# NIBP_Board_v1_2_0_feb2023.net
KiCad netlist of a schematic drawn in EAGLE
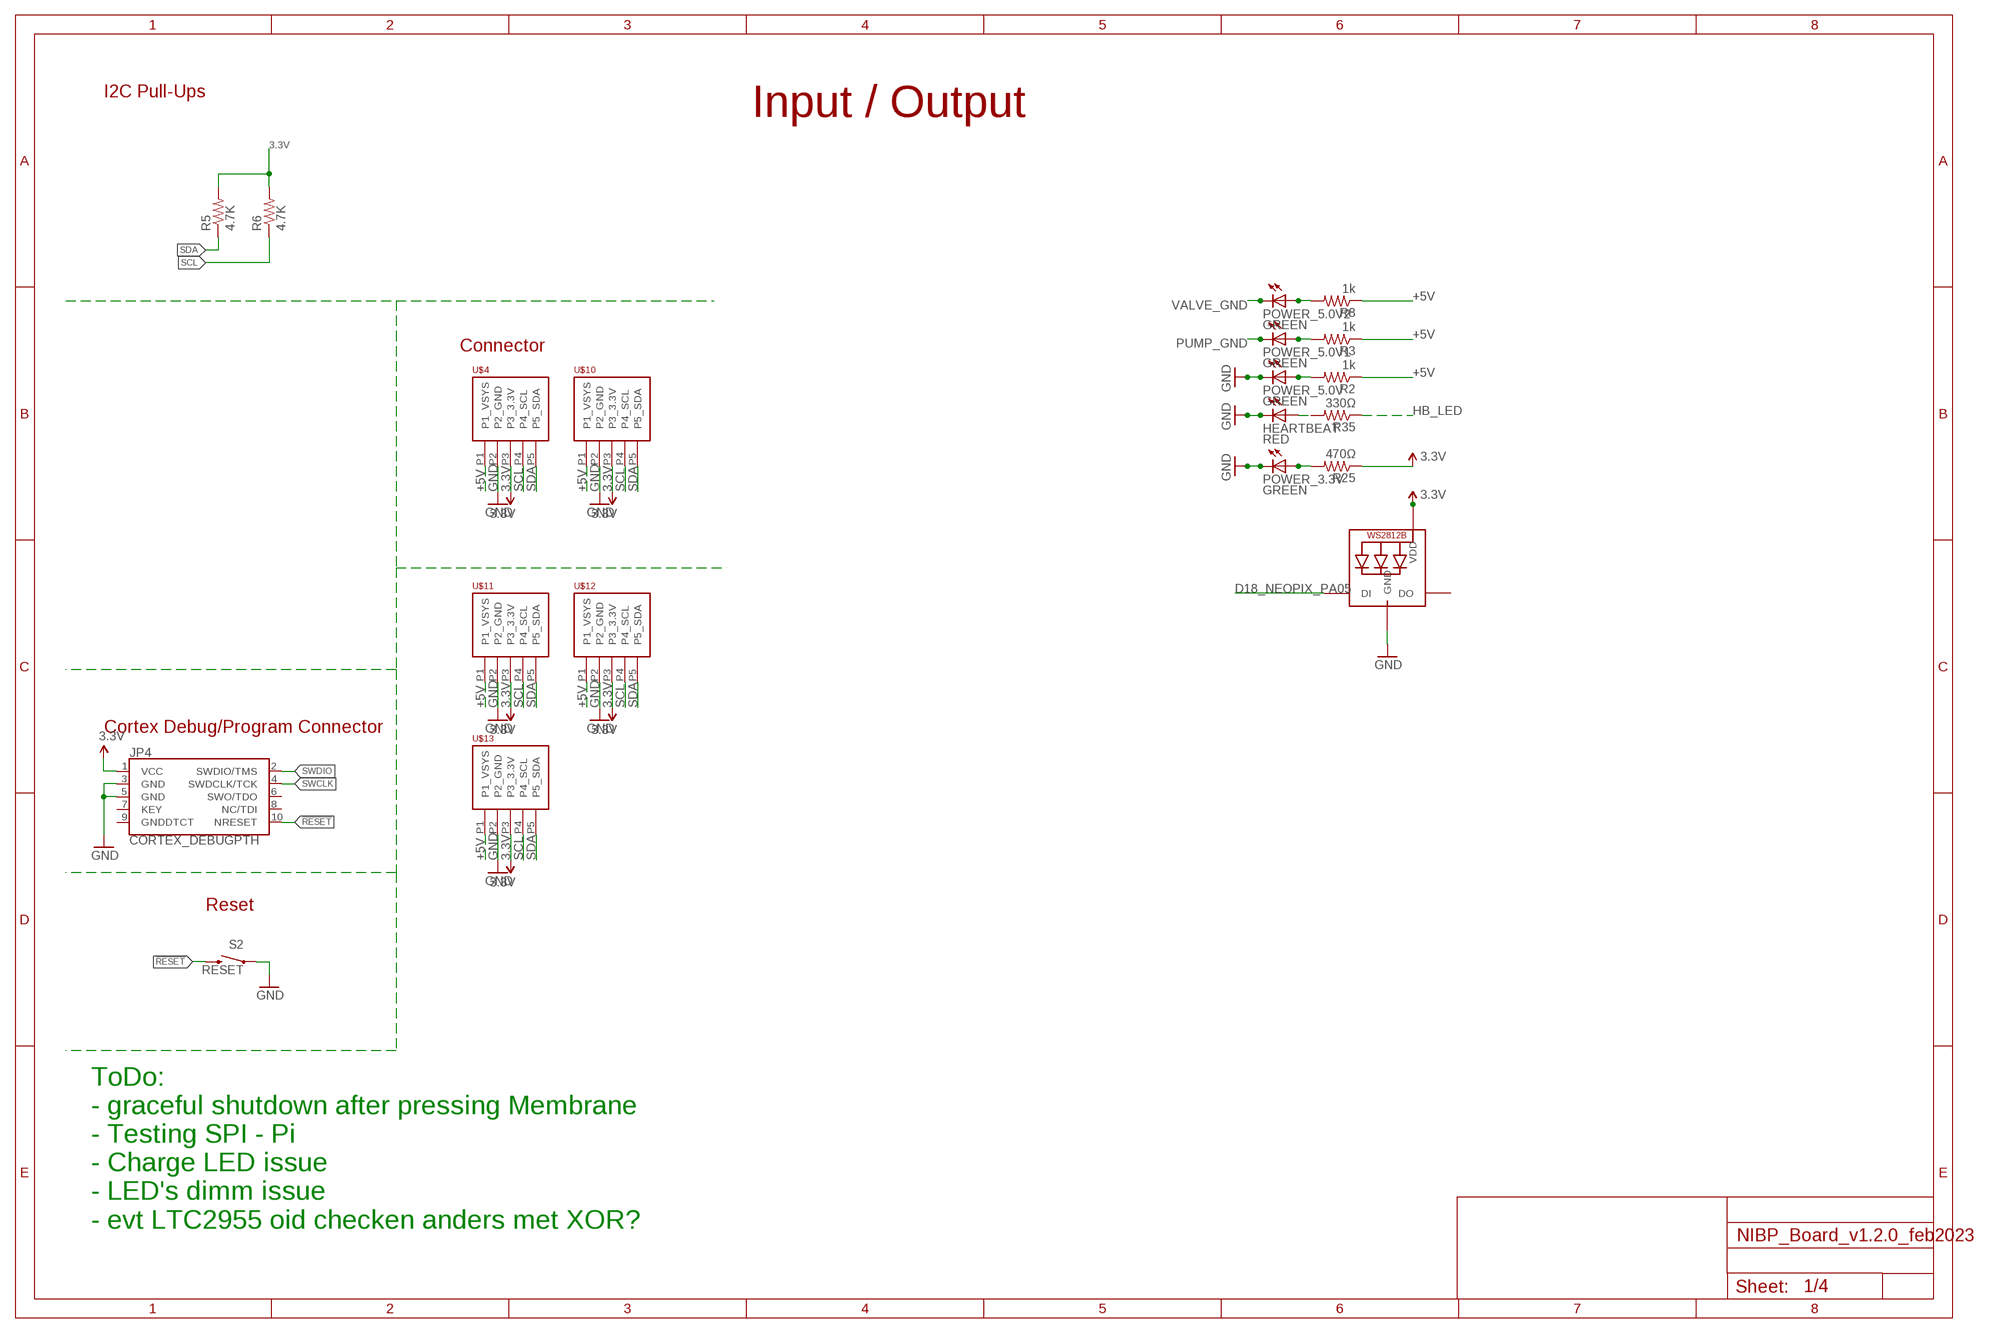
[diagram p0: schematic, sheet 1]
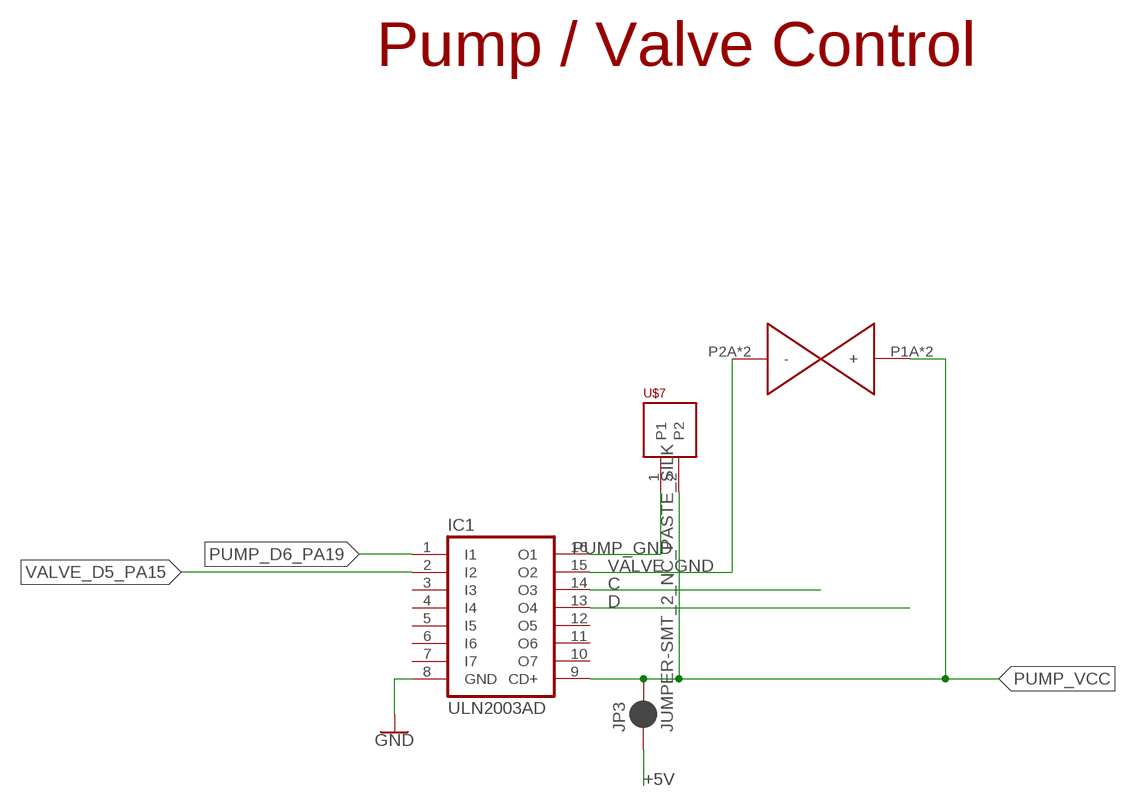
[diagram p1: schematic, sheet 2]
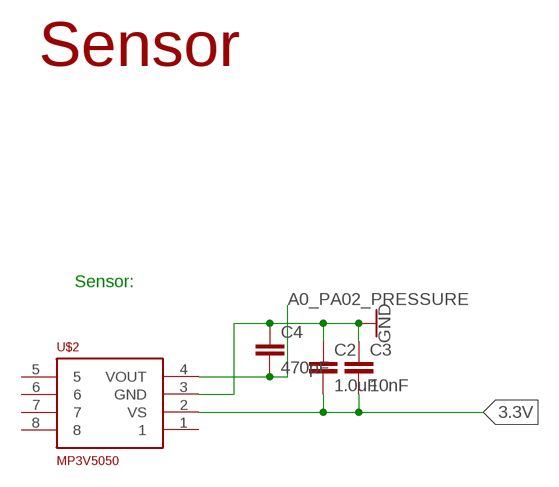
[diagram p2: schematic, sheet 3]
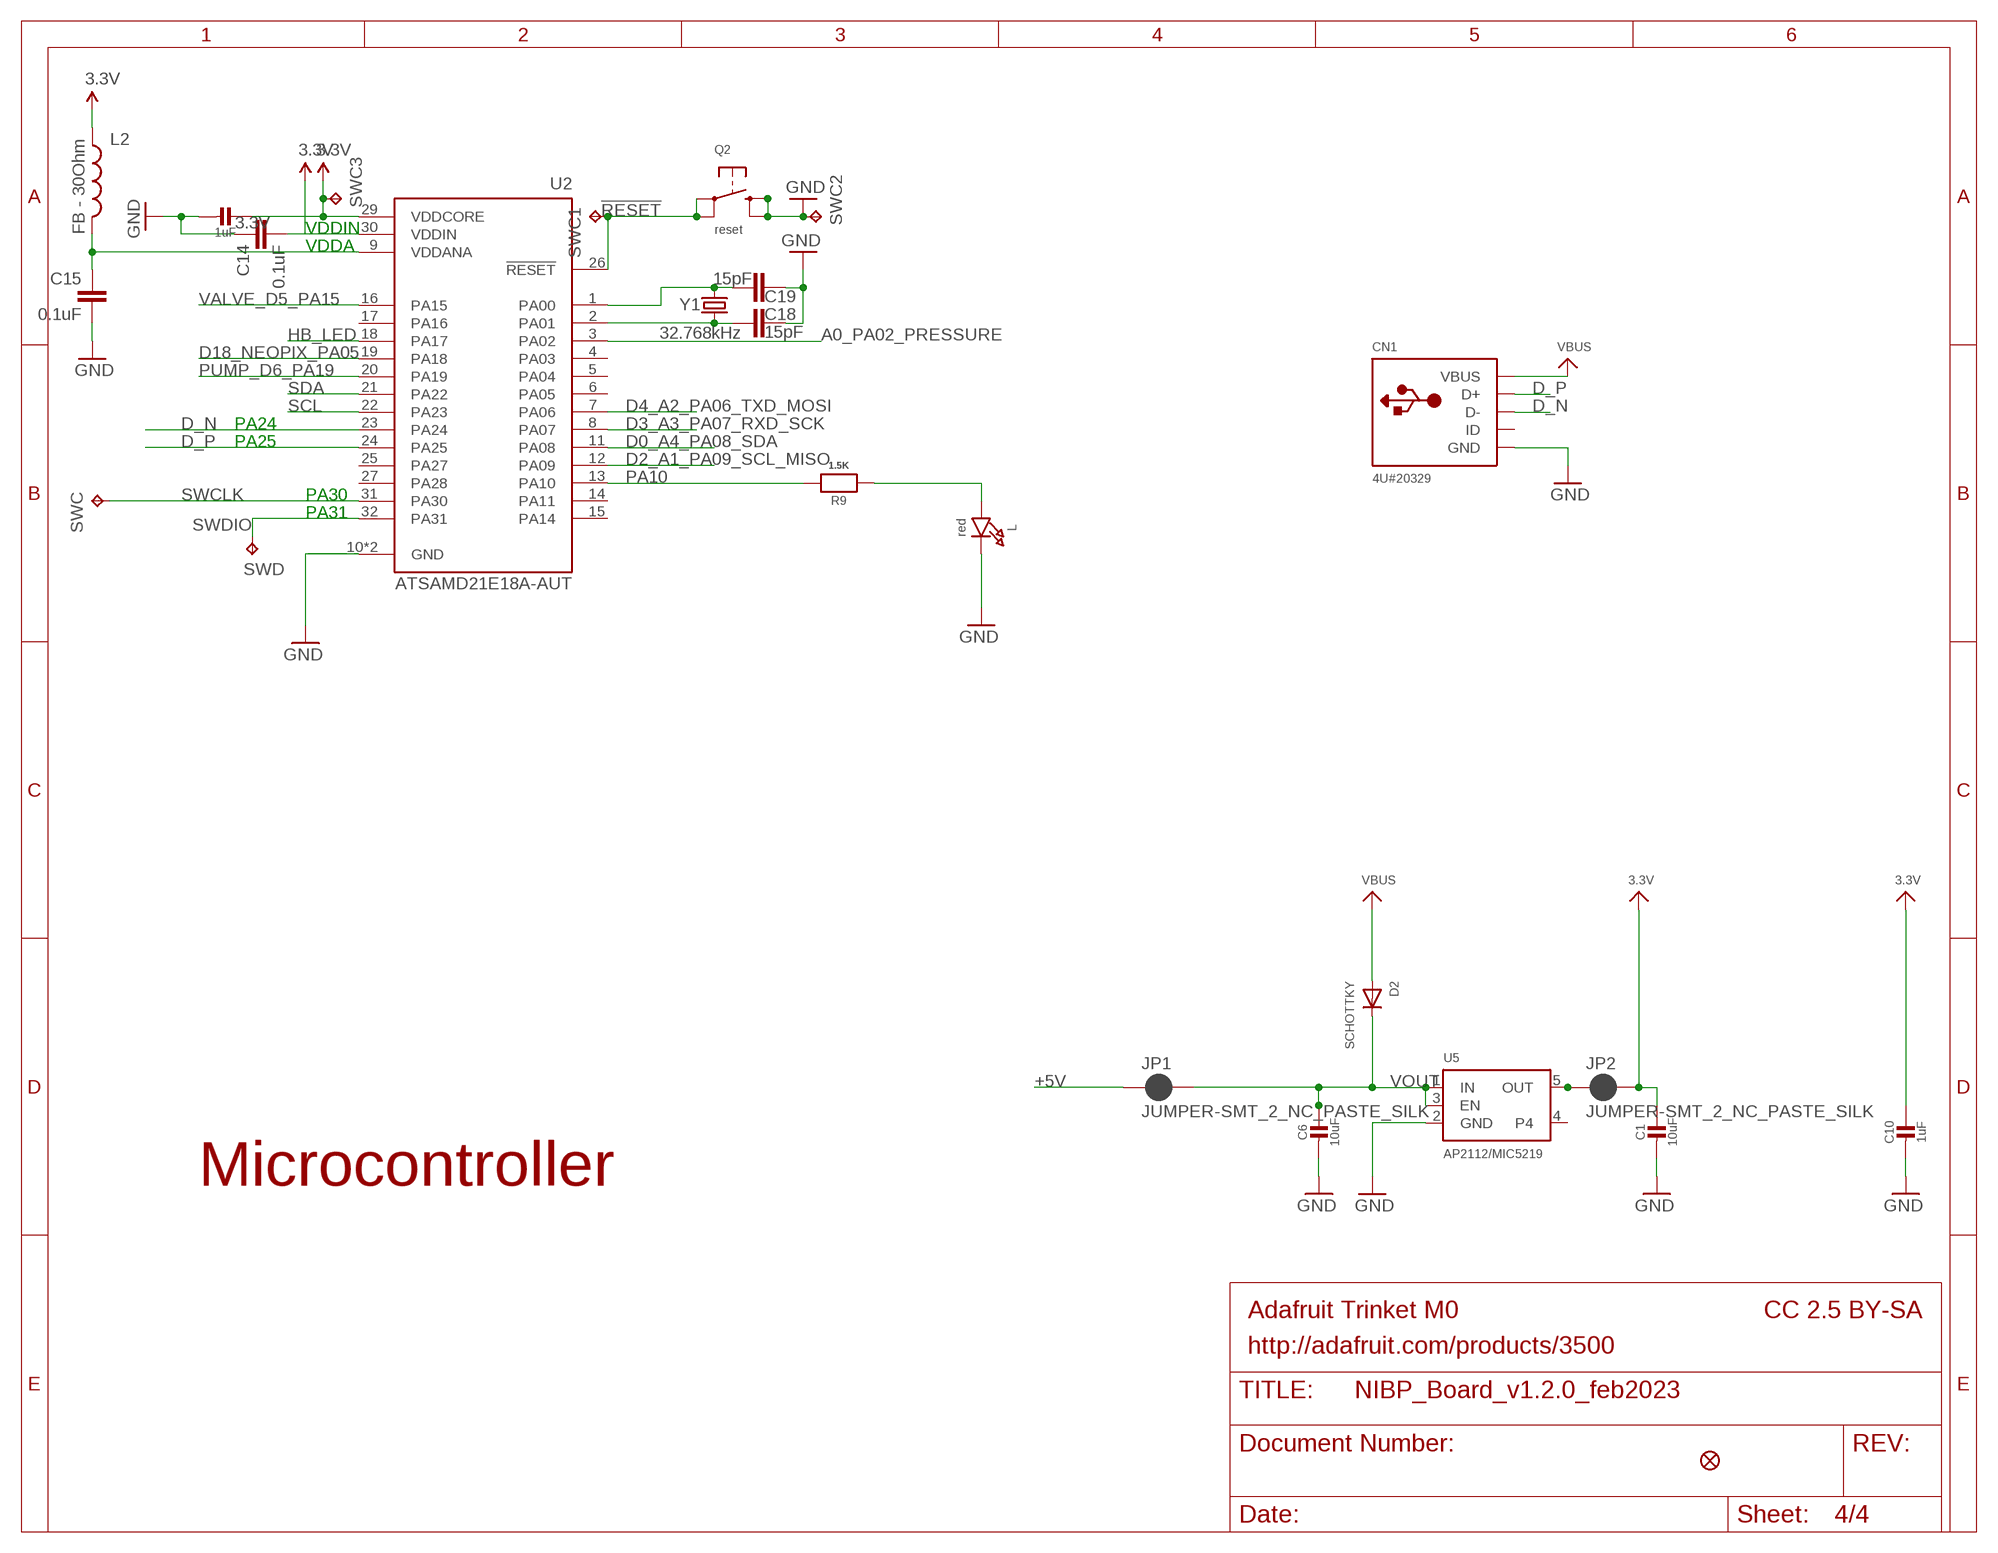
[diagram p3: schematic, sheet 4]

(export (version "E")
  (design (tool "Eeschema 10.0.6"))
  (components
    (comp (ref "C2")
      (value "1.0uF")
      (footprint "eagle-import:0603")
      (libsource (lib "eagle-import") (part "1.0UF-0603-16V-10%"))
    )
    (comp (ref "C3")
      (value "10nF")
      (footprint "eagle-import:0603")
      (libsource (lib "eagle-import") (part "10NF-0603-50V-10%"))
    )
    (comp (ref "C4")
      (value "470pF")
      (footprint "eagle-import:0603")
      (libsource (lib "eagle-import") (part "470PF-0603-50V-5%"))
    )
    (comp (ref "U$2")
      (value "MP3V5050")
      (footprint "eagle-import:PRESSURE_SENSOR")
      (libsource (lib "eagle-import") (part "MP3V5050"))
    )
    (comp (ref "C1")
      (value "10uF")
      (footprint "eagle-import:0805-NO")
      (libsource (lib "eagle-import") (part "CAP_CERAMIC0805-NOOUTLINE"))
    )
    (comp (ref "C6")
      (value "10uF")
      (footprint "eagle-import:0805-NO")
      (libsource (lib "eagle-import") (part "CAP_CERAMIC0805-NOOUTLINE"))
    )
    (comp (ref "C10")
      (value "1uF")
      (footprint "eagle-import:0603-NO")
      (libsource (lib "eagle-import") (part "CAP_CERAMIC0603_NO"))
    )
    (comp (ref "C13")
      (value "1uF")
      (footprint "eagle-import:0603-NO")
      (libsource (lib "eagle-import") (part "CAP_CERAMIC0603_NO"))
    )
    (comp (ref "C14")
      (value "0.1uF")
      (footprint "eagle-import:0402-CAP")
      (libsource (lib "eagle-import") (part "0.1UF-16V(+-10%)(0402)"))
    )
    (comp (ref "C15")
      (value "0.1uF")
      (footprint "eagle-import:0402-CAP")
      (libsource (lib "eagle-import") (part "0.1UF-16V(+-10%)(0402)"))
    )
    (comp (ref "C18")
      (value "15pF")
      (footprint "eagle-import:0402-CAP")
      (libsource (lib "eagle-import") (part "15PF-50V(+-5%)(0402)"))
    )
    (comp (ref "C19")
      (value "15pF")
      (footprint "eagle-import:0402-CAP")
      (libsource (lib "eagle-import") (part "15PF-50V(+-5%)(0402)"))
    )
    (comp (ref "CN1")
      (value "4U#20329")
      (footprint "eagle-import:4UCONN_20329_V2")
      (libsource (lib "eagle-import") (part "USB_MICRO_20329_V2"))
    )
    (comp (ref "D2")
      (value "SCHOTTKY")
      (footprint "eagle-import:SOD-123FL")
      (libsource (lib "eagle-import") (part "DIODE_SOD-123FL"))
    )
    (comp (ref "JP1")
      (value "JUMPER-SMT_2_NC_PASTE_SILK")
      (footprint "eagle-import:SMT-JUMPER_2_NC_PASTE_SILK")
      (libsource (lib "eagle-import") (part "JUMPER-SMT_2_NC_PASTE_SILK"))
    )
    (comp (ref "JP2")
      (value "JUMPER-SMT_2_NC_PASTE_SILK")
      (footprint "eagle-import:SMT-JUMPER_2_NC_PASTE_SILK")
      (libsource (lib "eagle-import") (part "JUMPER-SMT_2_NC_PASTE_SILK"))
    )
    (comp (ref "L")
      (value "red")
      (footprint "eagle-import:CHIPLED_0603_NOOUTLINE")
      (libsource (lib "eagle-import") (part "LED0603_NOOUTLINE"))
    )
    (comp (ref "L2")
      (value "FB - 30Ohm")
      (footprint "eagle-import:0603")
      (libsource (lib "eagle-import") (part "INDUCTOR0603"))
    )
    (comp (ref "Q2")
      (value "reset")
      (footprint "eagle-import:BTN_KMR2_4.6X2.8")
      (libsource (lib "eagle-import") (part "SWITCH_TACT_SMT4.6X2.8"))
    )
    (comp (ref "R9")
      (value "1.5K")
      (footprint "eagle-import:0603-NO")
      (libsource (lib "eagle-import") (part "RESISTOR_0603_NOOUT"))
    )
    (comp (ref "SWC")
      (value "TPB1,27")
      (footprint "eagle-import:B1,27")
      (libsource (lib "eagle-import") (part "TPB1,27"))
    )
    (comp (ref "SWC1")
      (value "TPB1,27")
      (footprint "eagle-import:B1,27")
      (libsource (lib "eagle-import") (part "TPB1,27"))
    )
    (comp (ref "SWC2")
      (value "TPB1,27")
      (footprint "eagle-import:B1,27")
      (libsource (lib "eagle-import") (part "TPB1,27"))
    )
    (comp (ref "SWC3")
      (value "TPB1,27")
      (footprint "eagle-import:B1,27")
      (libsource (lib "eagle-import") (part "TPB1,27"))
    )
    (comp (ref "SWD")
      (value "TPB1,27")
      (footprint "eagle-import:B1,27")
      (libsource (lib "eagle-import") (part "TPB1,27"))
    )
    (comp (ref "U$15")
      (value "FIDUCIAL_1MM")
      (footprint "eagle-import:FIDUCIAL_1MM")
      (libsource (lib "eagle-import") (part "FIDUCIAL_1MM"))
    )
    (comp (ref "U2")
      (value "ATSAMD21E18A-AUT")
      (footprint "eagle-import:QFP80P900X900X120-32N")
      (fields (field (name "MF") "Microchip") (field (name "MP") "ATSAMD21E18A-AU"))
      (libsource (lib "eagle-import") (part "ATSAMD21E18A-AUT"))
    )
    (comp (ref "U5")
      (value "AP2112/MIC5219")
      (footprint "eagle-import:SOT23-5")
      (libsource (lib "eagle-import") (part "VREG_SOT23-5"))
    )
    (comp (ref "Y1")
      (value "32.768kHz")
      (footprint "eagle-import:CRYSTAL-SMD-3.2X1.5MM")
      (libsource (lib "eagle-import") (part "CRYSTAL3.2X1.5MM"))
    )
    (comp (ref "IC1")
      (value "ULN2003AD")
      (footprint "eagle-import:SO16")
      (libsource (lib "eagle-import") (part "ULN2003AD"))
    )
    (comp (ref "JP3")
      (value "JUMPER-SMT_2_NC_PASTE_SILK")
      (footprint "eagle-import:SMT-JUMPER_2_NC_PASTE_SILK")
      (libsource (lib "eagle-import") (part "JUMPER-SMT_2_NC_PASTE_SILK"))
    )
    (comp (ref "U$6")
      (value "VALVE_NIBP")
      (footprint "eagle-import:VALVE_NIBP")
      (libsource (lib "eagle-import") (part "VALVE_NIBP"))
    )
    (comp (ref "U$7")
      (value "PHOENIX_PTSM_M2TH")
      (footprint "eagle-import:PTSM_M2_THRHOLE")
      (libsource (lib "eagle-import") (part "PHOENIX_PTSM_M2TH"))
    )
    (comp (ref "HEARTBEAT")
      (value "RED")
      (footprint "eagle-import:LED-0603")
      (libsource (lib "eagle-import") (part "LED0603"))
    )
    (comp (ref "JP4")
      (value "CORTEX_DEBUGPTH")
      (footprint "eagle-import:2X5-PTH-1.27MM")
      (libsource (lib "eagle-import") (part "CORTEX_DEBUGPTH"))
    )
    (comp (ref "LED1")
      (value "WS2812B3535")
      (footprint "eagle-import:LED3535")
      (libsource (lib "eagle-import") (part "WS2812B3535"))
    )
    (comp (ref "POWER_3.3V")
      (value "GREEN")
      (footprint "eagle-import:LED-0603")
      (libsource (lib "eagle-import") (part "LED0603"))
    )
    (comp (ref "POWER_5.0V")
      (value "GREEN")
      (footprint "eagle-import:LED-0603")
      (libsource (lib "eagle-import") (part "LED0603"))
    )
    (comp (ref "POWER_5.0V1")
      (value "GREEN")
      (footprint "eagle-import:LED-0603")
      (libsource (lib "eagle-import") (part "LED0603"))
    )
    (comp (ref "POWER_5.0V2")
      (value "GREEN")
      (footprint "eagle-import:LED-0603")
      (libsource (lib "eagle-import") (part "LED0603"))
    )
    (comp (ref "R2")
      (value "1k")
      (footprint "eagle-import:0603-RES")
      (libsource (lib "eagle-import") (part "10KOHM-1/10W-1%(0603)0603"))
    )
    (comp (ref "R3")
      (value "1k")
      (footprint "eagle-import:0603-RES")
      (libsource (lib "eagle-import") (part "10KOHM-1/10W-1%(0603)0603"))
    )
    (comp (ref "R5")
      (value "4.7K")
      (footprint "eagle-import:0603-RES@1")
      (libsource (lib "eagle-import") (part "4.7KOHM-1/10W-1%(0603)"))
    )
    (comp (ref "R6")
      (value "4.7K")
      (footprint "eagle-import:0603-RES@1")
      (libsource (lib "eagle-import") (part "4.7KOHM-1/10W-1%(0603)"))
    )
    (comp (ref "R8")
      (value "1k")
      (footprint "eagle-import:0603-RES")
      (libsource (lib "eagle-import") (part "10KOHM-1/10W-1%(0603)0603"))
    )
    (comp (ref "R25")
      (value "470Ω")
      (footprint "eagle-import:0603-RES")
      (libsource (lib "eagle-import") (part "10KOHM-1/10W-1%(0603)0603"))
    )
    (comp (ref "R35")
      (value "330Ω")
      (footprint "eagle-import:0603-RES")
      (libsource (lib "eagle-import") (part "10KOHM-1/10W-1%(0603)0603"))
    )
    (comp (ref "S2")
      (value "RESET")
      (footprint "eagle-import:TACTILE_SWITCH_SMD_4.6X2.8MM")
      (libsource (lib "eagle-import") (part "SWITCH-MOMENTARY-2SMD-4.6X2.8MM"))
    )
    (comp (ref "U$4")
      (value "PHOENIX_PTSM_M5_TH")
      (footprint "eagle-import:PTSM_M5_THRHOLE")
      (libsource (lib "eagle-import") (part "PHOENIX_PTSM_M5_TH"))
    )
    (comp (ref "U$10")
      (value "PHOENIX_PTSM_M5_TH")
      (footprint "eagle-import:PTSM_M5_THRHOLE")
      (libsource (lib "eagle-import") (part "PHOENIX_PTSM_M5_TH"))
    )
    (comp (ref "U$11")
      (value "PHOENIX_PTSM_M5_TH")
      (footprint "eagle-import:PTSM_M5_THRHOLE")
      (libsource (lib "eagle-import") (part "PHOENIX_PTSM_M5_TH"))
    )
    (comp (ref "U$12")
      (value "PHOENIX_PTSM_M5_TH")
      (footprint "eagle-import:PTSM_M5_THRHOLE")
      (libsource (lib "eagle-import") (part "PHOENIX_PTSM_M5_TH"))
    )
    (comp (ref "U$13")
      (value "PHOENIX_PTSM_M5_TH")
      (footprint "eagle-import:PTSM_M5_THRHOLE")
      (libsource (lib "eagle-import") (part "PHOENIX_PTSM_M5_TH"))
    )
  )
  (nets
    (net (code "1") (name "+5V") (class "Default")
      (node (ref "JP1") (pin "1") (pinfunction "1_1") (pintype "passive"))
      (node (ref "JP3") (pin "1") (pinfunction "1_1") (pintype "passive"))
      (node (ref "R2") (pin "1") (pinfunction "1_1") (pintype "passive"))
      (node (ref "R3") (pin "1") (pinfunction "1_1") (pintype "passive"))
      (node (ref "R8") (pin "1") (pinfunction "1_1") (pintype "passive"))
      (node (ref "U$10") (pin "P1") (pinfunction "P1_VSYS_P1") (pintype "power_in"))
      (node (ref "U$11") (pin "P1") (pinfunction "P1_VSYS_P1") (pintype "power_in"))
      (node (ref "U$12") (pin "P1") (pinfunction "P1_VSYS_P1") (pintype "power_in"))
      (node (ref "U$13") (pin "P1") (pinfunction "P1_VSYS_P1") (pintype "power_in"))
      (node (ref "U$4") (pin "P1") (pinfunction "P1_VSYS_P1") (pintype "power_in"))
    )
    (net (code "2") (name "3.3V") (class "Default")
      (node (ref "C1") (pin "1") (pinfunction "1_1") (pintype "passive"))
      (node (ref "C10") (pin "1") (pinfunction "1_1") (pintype "passive"))
      (node (ref "C13") (pin "1") (pinfunction "1_1") (pintype "passive"))
      (node (ref "C2") (pin "2") (pinfunction "2_2") (pintype "passive"))
      (node (ref "C3") (pin "2") (pinfunction "2_2") (pintype "passive"))
      (node (ref "JP2") (pin "2") (pinfunction "2_2") (pintype "passive"))
      (node (ref "JP4") (pin "1") (pinfunction "VCC_1") (pintype "bidirectional"))
      (node (ref "L2") (pin "1") (pinfunction "1_1") (pintype "passive"))
      (node (ref "LED1") (pin "2") (pinfunction "VDD_2") (pintype "power_in"))
      (node (ref "R25") (pin "1") (pinfunction "1_1") (pintype "passive"))
      (node (ref "R5") (pin "2") (pinfunction "2_2") (pintype "passive"))
      (node (ref "R6") (pin "2") (pinfunction "2_2") (pintype "passive"))
      (node (ref "SWC3") (pin "TP") (pinfunction "TP_TP") (pintype "input"))
      (node (ref "U$10") (pin "P3") (pinfunction "P3_3.3V_P3") (pintype "power_in"))
      (node (ref "U$11") (pin "P3") (pinfunction "P3_3.3V_P3") (pintype "power_in"))
      (node (ref "U$12") (pin "P3") (pinfunction "P3_3.3V_P3") (pintype "power_in"))
      (node (ref "U$13") (pin "P3") (pinfunction "P3_3.3V_P3") (pintype "power_in"))
      (node (ref "U$2") (pin "2") (pinfunction "VS_2") (pintype "bidirectional"))
      (node (ref "U$4") (pin "P3") (pinfunction "P3_3.3V_P3") (pintype "power_in"))
      (node (ref "U2") (pin "29") (pinfunction "VDDCORE_29") (pintype "power_in"))
    )
    (net (code "3") (name "A0_PA02_PRESSURE") (class "Default")
      (node (ref "C4") (pin "2") (pinfunction "2_2") (pintype "passive"))
      (node (ref "U$2") (pin "4") (pinfunction "VOUT_4") (pintype "bidirectional"))
      (node (ref "U2") (pin "3") (pinfunction "PA02_3") (pintype "bidirectional"))
    )
    (net (code "4") (name "C") (class "Default")
      (node (ref "IC1") (pin "14") (pinfunction "O3_14") (pintype "open_collector"))
    )
    (net (code "5") (name "D") (class "Default")
      (node (ref "IC1") (pin "13") (pinfunction "O4_13") (pintype "open_collector"))
    )
    (net (code "6") (name "D0_A4_PA08_SDA") (class "Default")
      (node (ref "U2") (pin "11") (pinfunction "PA08_11") (pintype "bidirectional"))
    )
    (net (code "7") (name "D2_A1_PA09_SCL_MISO") (class "Default")
      (node (ref "U2") (pin "12") (pinfunction "PA09_12") (pintype "bidirectional"))
    )
    (net (code "8") (name "D3_A3_PA07_RXD_SCK") (class "Default")
      (node (ref "U2") (pin "8") (pinfunction "PA07_8") (pintype "bidirectional"))
    )
    (net (code "9") (name "D4_A2_PA06_TXD_MOSI") (class "Default")
      (node (ref "U2") (pin "7") (pinfunction "PA06_7") (pintype "bidirectional"))
    )
    (net (code "10") (name "D18_NEOPIX_PA05") (class "Default")
      (node (ref "LED1") (pin "1") (pinfunction "DI_1") (pintype "input"))
      (node (ref "U2") (pin "19") (pinfunction "PA18_19") (pintype "bidirectional"))
    )
    (net (code "11") (name "D_N") (class "Default")
      (node (ref "CN1") (pin "D-") (pinfunction "D-_D-") (pintype "bidirectional"))
      (node (ref "U2") (pin "23") (pinfunction "PA24_23") (pintype "bidirectional"))
    )
    (net (code "12") (name "D_P") (class "Default")
      (node (ref "CN1") (pin "D+") (pinfunction "D+_D+") (pintype "bidirectional"))
      (node (ref "U2") (pin "24") (pinfunction "PA25_24") (pintype "bidirectional"))
    )
    (net (code "13") (name "GND") (class "Default")
      (node (ref "C1") (pin "2") (pinfunction "2_2") (pintype "passive"))
      (node (ref "C10") (pin "2") (pinfunction "2_2") (pintype "passive"))
      (node (ref "C13") (pin "2") (pinfunction "2_2") (pintype "passive"))
      (node (ref "C14") (pin "1") (pinfunction "1_1") (pintype "passive"))
      (node (ref "C15") (pin "2") (pinfunction "2_2") (pintype "passive"))
      (node (ref "C18") (pin "1") (pinfunction "1_1") (pintype "passive"))
      (node (ref "C19") (pin "2") (pinfunction "2_2") (pintype "passive"))
      (node (ref "C2") (pin "1") (pinfunction "1_1") (pintype "passive"))
      (node (ref "C3") (pin "1") (pinfunction "1_1") (pintype "passive"))
      (node (ref "C4") (pin "1") (pinfunction "1_1") (pintype "passive"))
      (node (ref "C6") (pin "2") (pinfunction "2_2") (pintype "passive"))
      (node (ref "CN1") (pin "BASE@1") (pinfunction "GND_BASE@1") (pintype "power_in"))
      (node (ref "CN1") (pin "BASE@2") (pinfunction "GND_BASE@2") (pintype "power_in"))
      (node (ref "CN1") (pin "GND") (pinfunction "GND_GND") (pintype "power_in"))
      (node (ref "CN1") (pin "SPRT@1") (pinfunction "GND_SPRT@1") (pintype "power_in"))
      (node (ref "CN1") (pin "SPRT@2") (pinfunction "GND_SPRT@2") (pintype "power_in"))
      (node (ref "CN1") (pin "SPRT@3") (pinfunction "GND_SPRT@3") (pintype "power_in"))
      (node (ref "CN1") (pin "SPRT@4") (pinfunction "GND_SPRT@4") (pintype "power_in"))
      (node (ref "HEARTBEAT") (pin "C") (pinfunction "C_C") (pintype "passive"))
      (node (ref "IC1") (pin "8") (pinfunction "GND_8") (pintype "power_in"))
      (node (ref "JP4") (pin "3") (pinfunction "GND_3") (pintype "bidirectional"))
      (node (ref "JP4") (pin "5") (pinfunction "GND_5") (pintype "bidirectional"))
      (node (ref "L") (pin "C") (pinfunction "C_C") (pintype "passive"))
      (node (ref "LED1") (pin "4") (pinfunction "GND_4") (pintype "power_in"))
      (node (ref "POWER_3.3V") (pin "C") (pinfunction "C_C") (pintype "passive"))
      (node (ref "POWER_5.0V") (pin "C") (pinfunction "C_C") (pintype "passive"))
      (node (ref "Q2") (pin "B") (pinfunction "S_B") (pintype "passive"))
      (node (ref "Q2") (pin "B'") (pinfunction "S1_B'") (pintype "passive"))
      (node (ref "S2") (pin "1") (pinfunction "1_1") (pintype "passive"))
      (node (ref "S2") (pin "2") (pinfunction "1_2") (pintype "passive"))
      (node (ref "SWC2") (pin "TP") (pinfunction "TP_TP") (pintype "input"))
      (node (ref "U$10") (pin "P2") (pinfunction "P2_GND_P2") (pintype "power_in"))
      (node (ref "U$11") (pin "P2") (pinfunction "P2_GND_P2") (pintype "power_in"))
      (node (ref "U$12") (pin "P2") (pinfunction "P2_GND_P2") (pintype "power_in"))
      (node (ref "U$13") (pin "P2") (pinfunction "P2_GND_P2") (pintype "power_in"))
      (node (ref "U$2") (pin "3") (pinfunction "GND_3") (pintype "bidirectional"))
      (node (ref "U$4") (pin "P2") (pinfunction "P2_GND_P2") (pintype "power_in"))
      (node (ref "U2") (pin "10") (pinfunction "GND_10") (pintype "power_in"))
      (node (ref "U2") (pin "28") (pinfunction "GND_28") (pintype "power_in"))
      (node (ref "U5") (pin "2") (pinfunction "GND_2") (pintype "power_in"))
    )
    (net (code "14") (name "HB_LED") (class "Default")
      (node (ref "R35") (pin "1") (pinfunction "1_1") (pintype "passive"))
      (node (ref "U2") (pin "18") (pinfunction "PA17_18") (pintype "bidirectional"))
    )
    (net (code "15") (name "Net-(HEARTBEAT-PadA)") (class "Default")
      (node (ref "HEARTBEAT") (pin "A") (pinfunction "A_A") (pintype "passive"))
      (node (ref "R35") (pin "2") (pinfunction "2_2") (pintype "passive"))
    )
    (net (code "16") (name "Net-(L-PadA)") (class "Default")
      (node (ref "L") (pin "A") (pinfunction "A_A") (pintype "passive"))
      (node (ref "R9") (pin "1") (pinfunction "1_1") (pintype "passive"))
    )
    (net (code "17") (name "Net-(POWER_3.3V-PadA)") (class "Default")
      (node (ref "POWER_3.3V") (pin "A") (pinfunction "A_A") (pintype "passive"))
      (node (ref "R25") (pin "2") (pinfunction "2_2") (pintype "passive"))
    )
    (net (code "18") (name "Net-(POWER_5.0V-PadA)") (class "Default")
      (node (ref "POWER_5.0V") (pin "A") (pinfunction "A_A") (pintype "passive"))
      (node (ref "R2") (pin "2") (pinfunction "2_2") (pintype "passive"))
    )
    (net (code "19") (name "Net-(POWER_5.0V1-PadA)") (class "Default")
      (node (ref "POWER_5.0V1") (pin "A") (pinfunction "A_A") (pintype "passive"))
      (node (ref "R3") (pin "2") (pinfunction "2_2") (pintype "passive"))
    )
    (net (code "20") (name "Net-(POWER_5.0V2-PadA)") (class "Default")
      (node (ref "POWER_5.0V2") (pin "A") (pinfunction "A_A") (pintype "passive"))
      (node (ref "R8") (pin "2") (pinfunction "2_2") (pintype "passive"))
    )
    (net (code "21") (name "Net-(U2-PA00)") (class "Default")
      (node (ref "C19") (pin "1") (pinfunction "1_1") (pintype "passive"))
      (node (ref "U2") (pin "1") (pinfunction "PA00_1") (pintype "bidirectional"))
      (node (ref "Y1") (pin "P$1") (pinfunction "1_P$1") (pintype "passive"))
    )
    (net (code "22") (name "Net-(U2-PA01)") (class "Default")
      (node (ref "C18") (pin "2") (pinfunction "2_2") (pintype "passive"))
      (node (ref "U2") (pin "2") (pinfunction "PA01_2") (pintype "bidirectional"))
      (node (ref "Y1") (pin "P$2") (pinfunction "2_P$2") (pintype "passive"))
    )
    (net (code "23") (name "Net-(U2-VDDANA)") (class "Default")
      (node (ref "C15") (pin "1") (pinfunction "1_1") (pintype "passive"))
      (node (ref "L2") (pin "2") (pinfunction "2_2") (pintype "passive"))
      (node (ref "U2") (pin "9") (pinfunction "VDDANA_9") (pintype "power_in"))
    )
    (net (code "24") (name "Net-(U2-VDDIN)") (class "Default")
      (node (ref "C14") (pin "2") (pinfunction "2_2") (pintype "passive"))
      (node (ref "U2") (pin "30") (pinfunction "VDDIN_30") (pintype "power_in"))
    )
    (net (code "25") (name "Net-(U5-OUT)") (class "Default")
      (node (ref "JP2") (pin "1") (pinfunction "1_1") (pintype "passive"))
      (node (ref "U5") (pin "5") (pinfunction "OUT_5") (pintype "power_in"))
    )
    (net (code "26") (name "PA10") (class "Default")
      (node (ref "R9") (pin "2") (pinfunction "2_2") (pintype "passive"))
      (node (ref "U2") (pin "13") (pinfunction "PA10_13") (pintype "bidirectional"))
    )
    (net (code "27") (name "PUMP_D6_PA19") (class "Default")
      (node (ref "IC1") (pin "1") (pinfunction "I1_1") (pintype "input"))
      (node (ref "U2") (pin "20") (pinfunction "PA19_20") (pintype "bidirectional"))
    )
    (net (code "28") (name "PUMP_GND") (class "Default")
      (node (ref "IC1") (pin "16") (pinfunction "O1_16") (pintype "open_collector"))
      (node (ref "POWER_5.0V1") (pin "C") (pinfunction "C_C") (pintype "passive"))
      (node (ref "U$7") (pin "1") (pinfunction "P1_1") (pintype "bidirectional"))
    )
    (net (code "29") (name "PUMP_VCC") (class "Default")
      (node (ref "IC1") (pin "9") (pinfunction "CD+_9") (pintype "passive"))
      (node (ref "JP3") (pin "2") (pinfunction "2_2") (pintype "passive"))
      (node (ref "U$6") (pin "P1A") (pinfunction "+_P1A") (pintype "power_in"))
      (node (ref "U$6") (pin "P1B") (pinfunction "+_P1B") (pintype "power_in"))
      (node (ref "U$7") (pin "2") (pinfunction "P2_2") (pintype "bidirectional"))
    )
    (net (code "30") (name "SCL") (class "Default")
      (node (ref "R6") (pin "1") (pinfunction "1_1") (pintype "passive"))
      (node (ref "U$10") (pin "P4") (pinfunction "P4_SCL_P4") (pintype "bidirectional"))
      (node (ref "U$11") (pin "P4") (pinfunction "P4_SCL_P4") (pintype "bidirectional"))
      (node (ref "U$12") (pin "P4") (pinfunction "P4_SCL_P4") (pintype "bidirectional"))
      (node (ref "U$13") (pin "P4") (pinfunction "P4_SCL_P4") (pintype "bidirectional"))
      (node (ref "U$4") (pin "P4") (pinfunction "P4_SCL_P4") (pintype "bidirectional"))
      (node (ref "U2") (pin "22") (pinfunction "PA23_22") (pintype "bidirectional"))
    )
    (net (code "31") (name "SDA") (class "Default")
      (node (ref "R5") (pin "1") (pinfunction "1_1") (pintype "passive"))
      (node (ref "U$10") (pin "P5") (pinfunction "P5_SDA_P5") (pintype "bidirectional"))
      (node (ref "U$11") (pin "P5") (pinfunction "P5_SDA_P5") (pintype "bidirectional"))
      (node (ref "U$12") (pin "P5") (pinfunction "P5_SDA_P5") (pintype "bidirectional"))
      (node (ref "U$13") (pin "P5") (pinfunction "P5_SDA_P5") (pintype "bidirectional"))
      (node (ref "U$4") (pin "P5") (pinfunction "P5_SDA_P5") (pintype "bidirectional"))
      (node (ref "U2") (pin "21") (pinfunction "PA22_21") (pintype "bidirectional"))
    )
    (net (code "32") (name "SWCLK") (class "Default")
      (node (ref "JP4") (pin "4") (pinfunction "SWDCLK/TCK_4") (pintype "bidirectional"))
      (node (ref "SWC") (pin "TP") (pinfunction "TP_TP") (pintype "input"))
      (node (ref "U2") (pin "31") (pinfunction "PA30_31") (pintype "bidirectional"))
    )
    (net (code "33") (name "SWDIO") (class "Default")
      (node (ref "JP4") (pin "2") (pinfunction "SWDIO/TMS_2") (pintype "bidirectional"))
      (node (ref "SWD") (pin "TP") (pinfunction "TP_TP") (pintype "input"))
      (node (ref "U2") (pin "32") (pinfunction "PA31_32") (pintype "bidirectional"))
    )
    (net (code "34") (name "VALVE_D5_PA15") (class "Default")
      (node (ref "IC1") (pin "2") (pinfunction "I2_2") (pintype "input"))
      (node (ref "U2") (pin "16") (pinfunction "PA15_16") (pintype "bidirectional"))
    )
    (net (code "35") (name "VALVE_GND") (class "Default")
      (node (ref "IC1") (pin "15") (pinfunction "O2_15") (pintype "open_collector"))
      (node (ref "POWER_5.0V2") (pin "C") (pinfunction "C_C") (pintype "passive"))
      (node (ref "U$6") (pin "P2A") (pinfunction "-_P2A") (pintype "power_in"))
      (node (ref "U$6") (pin "P2B") (pinfunction "-_P2B") (pintype "power_in"))
    )
    (net (code "36") (name "VBUS") (class "Default")
      (node (ref "CN1") (pin "VBUS") (pinfunction "VBUS_VBUS") (pintype "power_in"))
      (node (ref "D2") (pin "A") (pinfunction "A_A") (pintype "passive"))
    )
    (net (code "37") (name "VOUT") (class "Default")
      (node (ref "C6") (pin "1") (pinfunction "1_1") (pintype "passive"))
      (node (ref "D2") (pin "C") (pinfunction "C_C") (pintype "passive"))
      (node (ref "JP1") (pin "2") (pinfunction "2_2") (pintype "passive"))
      (node (ref "U5") (pin "1") (pinfunction "IN_1") (pintype "power_in"))
      (node (ref "U5") (pin "3") (pinfunction "EN_3") (pintype "input"))
    )
    (net (code "38") (name "unconnected-(CN1-PadID)") (class "Default")
      (node (ref "CN1") (pin "ID") (pinfunction "ID_ID") (pintype "bidirectional"))
    )
    (net (code "39") (name "unconnected-(IC1-I3-Pad3)") (class "Default")
      (node (ref "IC1") (pin "3") (pinfunction "I3_3") (pintype "input"))
    )
    (net (code "40") (name "unconnected-(IC1-I4-Pad4)") (class "Default")
      (node (ref "IC1") (pin "4") (pinfunction "I4_4") (pintype "input"))
    )
    (net (code "41") (name "unconnected-(IC1-I5-Pad5)") (class "Default")
      (node (ref "IC1") (pin "5") (pinfunction "I5_5") (pintype "input"))
    )
    (net (code "42") (name "unconnected-(IC1-I6-Pad6)") (class "Default")
      (node (ref "IC1") (pin "6") (pinfunction "I6_6") (pintype "input"))
    )
    (net (code "43") (name "unconnected-(IC1-I7-Pad7)") (class "Default")
      (node (ref "IC1") (pin "7") (pinfunction "I7_7") (pintype "input"))
    )
    (net (code "44") (name "unconnected-(IC1-O5-Pad12)") (class "Default")
      (node (ref "IC1") (pin "12") (pinfunction "O5_12") (pintype "open_collector"))
    )
    (net (code "45") (name "unconnected-(IC1-O6-Pad11)") (class "Default")
      (node (ref "IC1") (pin "11") (pinfunction "O6_11") (pintype "open_collector"))
    )
    (net (code "46") (name "unconnected-(IC1-O7-Pad10)") (class "Default")
      (node (ref "IC1") (pin "10") (pinfunction "O7_10") (pintype "open_collector"))
    )
    (net (code "47") (name "unconnected-(JP4-GNDDTCT-Pad9)") (class "Default")
      (node (ref "JP4") (pin "9") (pinfunction "GNDDTCT_9") (pintype "bidirectional"))
    )
    (net (code "48") (name "unconnected-(JP4-KEY-Pad7)") (class "Default")
      (node (ref "JP4") (pin "7") (pinfunction "KEY_7") (pintype "bidirectional"))
    )
    (net (code "49") (name "unconnected-(JP4-NC{slash}TDI-Pad8)") (class "Default")
      (node (ref "JP4") (pin "8") (pinfunction "NC/TDI_8") (pintype "bidirectional"))
    )
    (net (code "50") (name "unconnected-(JP4-SWO{slash}TDO-Pad6)") (class "Default")
      (node (ref "JP4") (pin "6") (pinfunction "SWO/TDO_6") (pintype "bidirectional"))
    )
    (net (code "51") (name "unconnected-(LED1-DO-Pad3)") (class "Default")
      (node (ref "LED1") (pin "3") (pinfunction "DO_3") (pintype "output"))
    )
    (net (code "52") (name "unconnected-(U$2-Pad1)") (class "Default")
      (node (ref "U$2") (pin "1") (pinfunction "1_1") (pintype "no_connect"))
    )
    (net (code "53") (name "unconnected-(U$2-Pad5)") (class "Default")
      (node (ref "U$2") (pin "5") (pinfunction "5_5") (pintype "no_connect"))
    )
    (net (code "54") (name "unconnected-(U$2-Pad6)") (class "Default")
      (node (ref "U$2") (pin "6") (pinfunction "6_6") (pintype "no_connect"))
    )
    (net (code "55") (name "unconnected-(U$2-Pad7)") (class "Default")
      (node (ref "U$2") (pin "7") (pinfunction "7_7") (pintype "no_connect"))
    )
    (net (code "56") (name "unconnected-(U$2-Pad8)") (class "Default")
      (node (ref "U$2") (pin "8") (pinfunction "8_8") (pintype "no_connect"))
    )
    (net (code "57") (name "unconnected-(U2-PA03-Pad4)") (class "Default")
      (node (ref "U2") (pin "4") (pinfunction "PA03_4") (pintype "bidirectional"))
    )
    (net (code "58") (name "unconnected-(U2-PA04-Pad5)") (class "Default")
      (node (ref "U2") (pin "5") (pinfunction "PA04_5") (pintype "bidirectional"))
    )
    (net (code "59") (name "unconnected-(U2-PA05-Pad6)") (class "Default")
      (node (ref "U2") (pin "6") (pinfunction "PA05_6") (pintype "bidirectional"))
    )
    (net (code "60") (name "unconnected-(U2-PA11-Pad14)") (class "Default")
      (node (ref "U2") (pin "14") (pinfunction "PA11_14") (pintype "bidirectional"))
    )
    (net (code "61") (name "unconnected-(U2-PA14-Pad15)") (class "Default")
      (node (ref "U2") (pin "15") (pinfunction "PA14_15") (pintype "bidirectional"))
    )
    (net (code "62") (name "unconnected-(U2-PA16-Pad17)") (class "Default")
      (node (ref "U2") (pin "17") (pinfunction "PA16_17") (pintype "bidirectional"))
    )
    (net (code "63") (name "unconnected-(U2-PA27-Pad25)") (class "Default")
      (node (ref "U2") (pin "25") (pinfunction "PA27_25") (pintype "bidirectional"))
    )
    (net (code "64") (name "unconnected-(U2-PA28-Pad27)") (class "Default")
      (node (ref "U2") (pin "27") (pinfunction "PA28_27") (pintype "bidirectional"))
    )
    (net (code "65") (name "unconnected-(U5-P4-Pad4)") (class "Default")
      (node (ref "U5") (pin "4") (pinfunction "P4_4") (pintype "bidirectional"))
    )
    (net (code "66") (name "~{RESET}") (class "Default")
      (node (ref "JP4") (pin "10") (pinfunction "NRESET_10") (pintype "bidirectional"))
      (node (ref "Q2") (pin "A") (pinfunction "P_A") (pintype "passive"))
      (node (ref "Q2") (pin "A'") (pinfunction "P1_A'") (pintype "passive"))
      (node (ref "S2") (pin "3") (pinfunction "2_3") (pintype "passive"))
      (node (ref "S2") (pin "4") (pinfunction "2_4") (pintype "passive"))
      (node (ref "SWC1") (pin "TP") (pinfunction "TP_TP") (pintype "input"))
      (node (ref "U2") (pin "26") (pinfunction "~{RESET}_26") (pintype "input"))
    )
  )
)
